# A1-A2_Power.net
KiCad netlist of a schematic drawn in Altium Designer
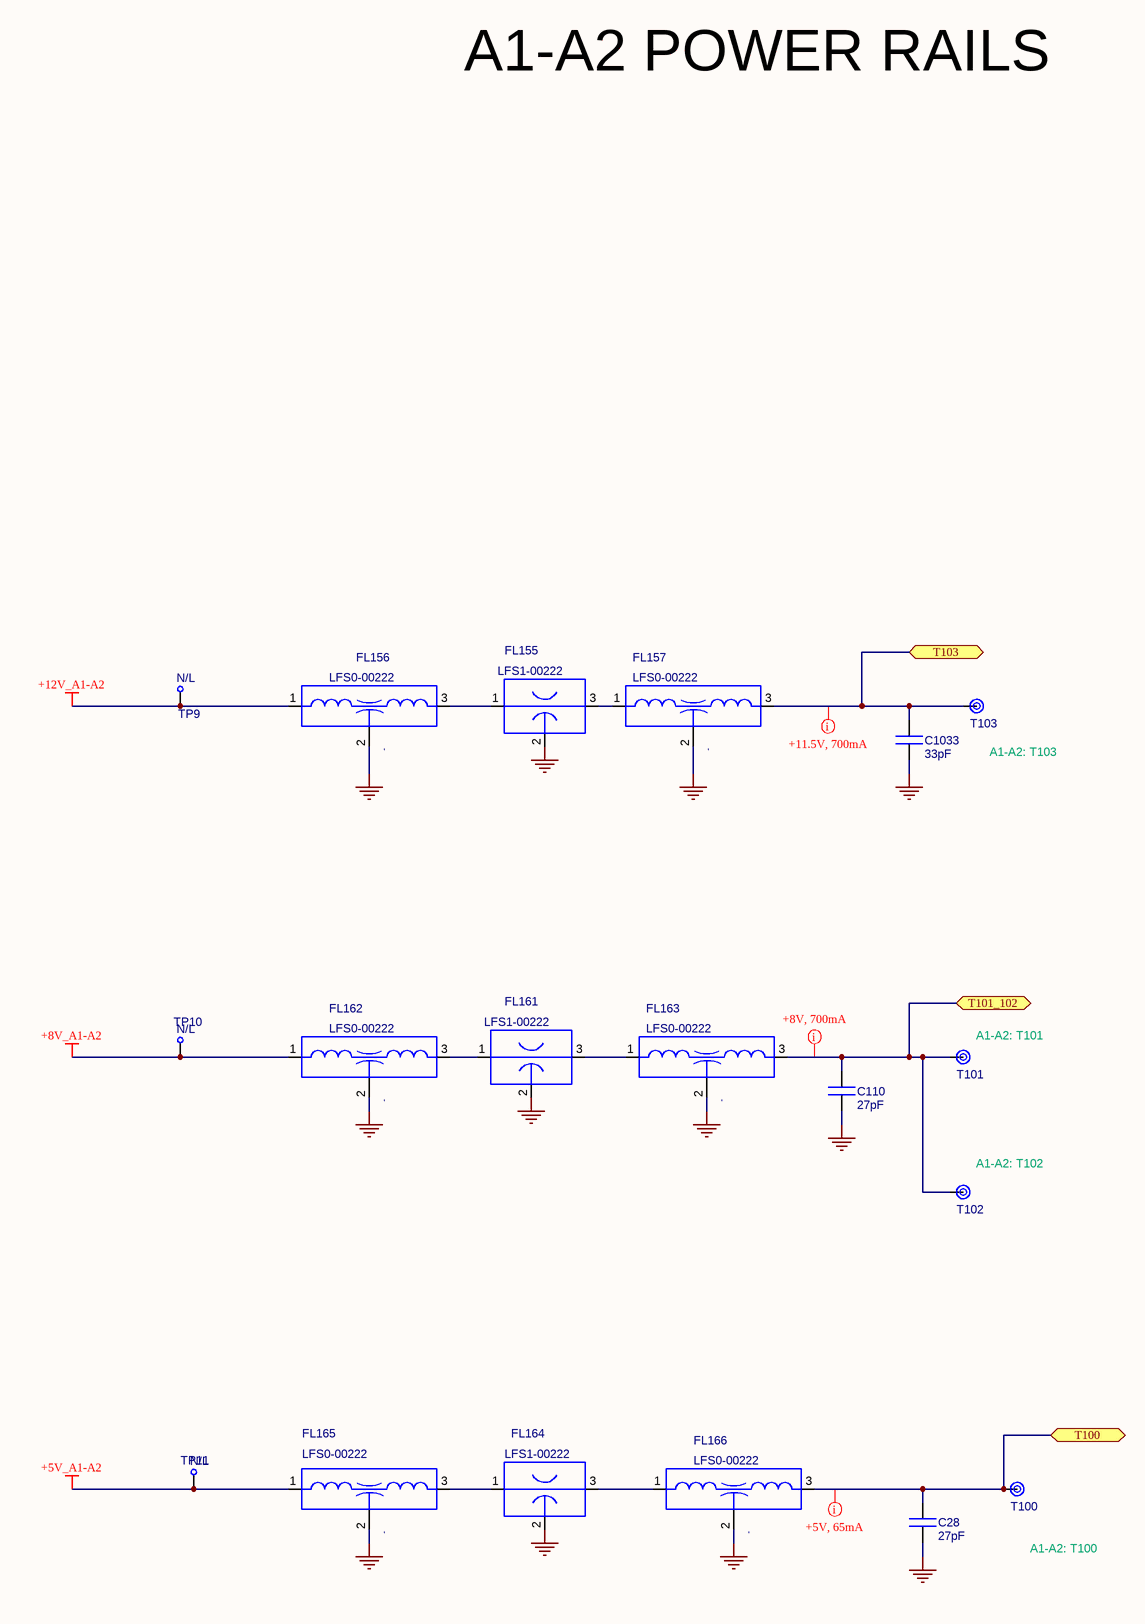
[diagram p0: A1-A2 Power.SchDoc]

(export (version "E")
  (design (tool "Eeschema 10.0.6"))
  (components
    (comp (ref "C28")
      (value "27pF")
      (footprint "CAP-0402-N")
      (description "27 PF;5%;COG;>50V;CHIP;0402")
      (fields (field (name "APPROVED") "CL"))
      (libsource (lib "Giga-tronics") (part "CK40-00270"))
    )
    (comp (ref "C110")
      (value "27pF")
      (footprint "CAP-0402-N")
      (description "27 PF;5%;COG;>50V;CHIP;0402")
      (fields (field (name "APPROVED") "CL"))
      (libsource (lib "Giga-tronics") (part "CK40-00270"))
    )
    (comp (ref "C1033")
      (value "33pF")
      (footprint "CAP-0402-N")
      (description "33 PF;5%;COG;>50V;CHIP;0402")
      (fields (field (name "APPROVED") "CL"))
      (libsource (lib "Giga-tronics") (part "CK40-00330"))
    )
    (comp (ref "FL155")
      (value "NFM18CC222R1C3")
      (footprint "FIL-NFL18C")
      (description "2200 PF FEED THRU FILTER 0603")
      (fields (field (name "G_PN") "LFS1-00222") (field (name "APPROVED") "NM"))
      (libsource (lib "Giga-tronics") (part "LFS1-00222"))
    )
    (comp (ref "FL156")
      (value "Filter EMI 2200PF,1206")
      (footprint "FIL-NFE31P-1206-4P")
      (fields (field (name "G_PN") "LFS0-00222") (field (name "APPROVED") "CL"))
      (libsource (lib "Giga-tronics") (part "LFS0-00222"))
    )
    (comp (ref "FL157")
      (value "Filter EMI 2200PF,1206")
      (footprint "FIL-NFE31P-1206-4P")
      (fields (field (name "G_PN") "LFS0-00222") (field (name "APPROVED") "CL"))
      (libsource (lib "Giga-tronics") (part "LFS0-00222"))
    )
    (comp (ref "FL161")
      (value "NFM18CC222R1C3")
      (footprint "FIL-NFL18C")
      (description "2200 PF FEED THRU FILTER 0603")
      (fields (field (name "G_PN") "LFS1-00222") (field (name "APPROVED") "NM"))
      (libsource (lib "Giga-tronics") (part "LFS1-00222"))
    )
    (comp (ref "FL162")
      (value "Filter EMI 2200PF,1206")
      (footprint "FIL-NFE31P-1206-4P")
      (fields (field (name "G_PN") "LFS0-00222") (field (name "APPROVED") "CL"))
      (libsource (lib "Giga-tronics") (part "LFS0-00222"))
    )
    (comp (ref "FL163")
      (value "Filter EMI 2200PF,1206")
      (footprint "FIL-NFE31P-1206-4P")
      (fields (field (name "G_PN") "LFS0-00222") (field (name "APPROVED") "CL"))
      (libsource (lib "Giga-tronics") (part "LFS0-00222"))
    )
    (comp (ref "FL164")
      (value "NFM18CC222R1C3")
      (footprint "FIL-NFL18C")
      (description "2200 PF FEED THRU FILTER 0603")
      (fields (field (name "G_PN") "LFS1-00222") (field (name "APPROVED") "NM"))
      (libsource (lib "Giga-tronics") (part "LFS1-00222"))
    )
    (comp (ref "FL165")
      (value "Filter EMI 2200PF,1206")
      (footprint "FIL-NFE31P-1206-4P")
      (fields (field (name "G_PN") "LFS0-00222") (field (name "APPROVED") "CL"))
      (libsource (lib "Giga-tronics") (part "LFS0-00222"))
    )
    (comp (ref "FL166")
      (value "Filter EMI 2200PF,1206")
      (footprint "FIL-NFE31P-1206-4P")
      (fields (field (name "G_PN") "LFS0-00222") (field (name "APPROVED") "CL"))
      (libsource (lib "Giga-tronics") (part "LFS0-00222"))
    )
    (comp (ref "T100")
      (value "A1-A2: T100")
      (footprint "JIB0-11254")
      (description "SOCKET;SINGLE;.018-.040 ID X .254;OPEN;GLD")
      (fields (field (name "APPROVED") "NM"))
      (libsource (lib "Giga-tronics") (part "JIB0-11254"))
    )
    (comp (ref "T101")
      (value "A1-A2: T101")
      (footprint "JIB0-11254")
      (description "SOCKET;SINGLE;.018-.040 ID X .254;OPEN;GLD")
      (fields (field (name "APPROVED") "NM"))
      (libsource (lib "Giga-tronics") (part "JIB0-11254"))
    )
    (comp (ref "T102")
      (value "A1-A2: T102")
      (footprint "JIB0-11254")
      (description "SOCKET;SINGLE;.018-.040 ID X .254;OPEN;GLD")
      (fields (field (name "APPROVED") "NM"))
      (libsource (lib "Giga-tronics") (part "JIB0-11254"))
    )
    (comp (ref "T103")
      (value "A1-A2: T103")
      (footprint "JIB0-11254")
      (description "SOCKET;SINGLE;.018-.040 ID X .254;OPEN;GLD")
      (fields (field (name "APPROVED") "NM"))
      (libsource (lib "Giga-tronics") (part "JIB0-11254"))
    )
    (comp (ref "TP9")
      (value ".")
      (footprint "TP-060")
      (fields (field (name "NOLOAD") "N/L") (field (name "APPROVED") "NM"))
      (libsource (lib "Giga-tronics") (part "TP-060"))
    )
    (comp (ref "TP10")
      (value ".")
      (footprint "TP-060")
      (fields (field (name "NOLOAD") "N/L") (field (name "APPROVED") "NM"))
      (libsource (lib "Giga-tronics") (part "TP-060"))
    )
    (comp (ref "TP11")
      (value ".")
      (footprint "TP-060")
      (fields (field (name "NOLOAD") "N/L") (field (name "APPROVED") "NM"))
      (libsource (lib "Giga-tronics") (part "TP-060"))
    )
  )
  (nets
    (net (code "1") (name "+5V_A1-A2") (class "Default")
      (node (ref "FL165") (pin "1") (pinfunction "IN_1") (pintype "passive"))
      (node (ref "TP11") (pin "1") (pinfunction "1_1") (pintype "passive"))
    )
    (net (code "2") (name "+8V_A1-A2") (class "Default")
      (node (ref "FL162") (pin "1") (pinfunction "IN_1") (pintype "passive"))
      (node (ref "TP10") (pin "1") (pinfunction "1_1") (pintype "passive"))
    )
    (net (code "3") (name "+12V_A1-A2") (class "Default")
      (node (ref "FL156") (pin "1") (pinfunction "IN_1") (pintype "passive"))
      (node (ref "TP9") (pin "1") (pinfunction "1_1") (pintype "passive"))
    )
    (net (code "4") (name "/T100") (class "Default")
      (node (ref "C28") (pin "1") (pintype "passive"))
      (node (ref "FL166") (pin "3") (pinfunction "OUT_3") (pintype "passive"))
      (node (ref "T100") (pin "1") (pintype "passive"))
    )
    (net (code "5") (name "/T101_102") (class "Default")
      (node (ref "C110") (pin "2") (pintype "passive"))
      (node (ref "FL163") (pin "3") (pinfunction "OUT_3") (pintype "passive"))
      (node (ref "T101") (pin "1") (pintype "passive"))
      (node (ref "T102") (pin "1") (pintype "passive"))
    )
    (net (code "6") (name "/T103") (class "Default")
      (node (ref "C1033") (pin "2") (pintype "passive"))
      (node (ref "FL157") (pin "3") (pinfunction "OUT_3") (pintype "passive"))
      (node (ref "T103") (pin "1") (pintype "passive"))
    )
    (net (code "7") (name "GND") (class "Default")
      (node (ref "C1033") (pin "1") (pintype "passive"))
      (node (ref "C110") (pin "1") (pintype "passive"))
      (node (ref "C28") (pin "2") (pintype "passive"))
      (node (ref "FL155") (pin "2") (pintype "passive"))
      (node (ref "FL156") (pin "2") (pinfunction "GND_2") (pintype "passive"))
      (node (ref "FL157") (pin "2") (pinfunction "GND_2") (pintype "passive"))
      (node (ref "FL161") (pin "2") (pintype "passive"))
      (node (ref "FL162") (pin "2") (pinfunction "GND_2") (pintype "passive"))
      (node (ref "FL163") (pin "2") (pinfunction "GND_2") (pintype "passive"))
      (node (ref "FL164") (pin "2") (pintype "passive"))
      (node (ref "FL165") (pin "2") (pinfunction "GND_2") (pintype "passive"))
      (node (ref "FL166") (pin "2") (pinfunction "GND_2") (pintype "passive"))
    )
    (net (code "8") (name "Net-(FL156-OUT)") (class "Default")
      (node (ref "FL155") (pin "1") (pintype "passive"))
      (node (ref "FL156") (pin "3") (pinfunction "OUT_3") (pintype "passive"))
    )
    (net (code "9") (name "Net-(FL157-IN)") (class "Default")
      (node (ref "FL155") (pin "3") (pintype "passive"))
      (node (ref "FL157") (pin "1") (pinfunction "IN_1") (pintype "passive"))
    )
    (net (code "10") (name "Net-(FL162-OUT)") (class "Default")
      (node (ref "FL161") (pin "1") (pintype "passive"))
      (node (ref "FL162") (pin "3") (pinfunction "OUT_3") (pintype "passive"))
    )
    (net (code "11") (name "Net-(FL163-IN)") (class "Default")
      (node (ref "FL161") (pin "3") (pintype "passive"))
      (node (ref "FL163") (pin "1") (pinfunction "IN_1") (pintype "passive"))
    )
    (net (code "12") (name "Net-(FL165-OUT)") (class "Default")
      (node (ref "FL164") (pin "1") (pintype "passive"))
      (node (ref "FL165") (pin "3") (pinfunction "OUT_3") (pintype "passive"))
    )
    (net (code "13") (name "Net-(FL166-IN)") (class "Default")
      (node (ref "FL164") (pin "3") (pintype "passive"))
      (node (ref "FL166") (pin "1") (pinfunction "IN_1") (pintype "passive"))
    )
  )
)
